# TopLevel.net
KiCad netlist of a schematic drawn in Altium Designer
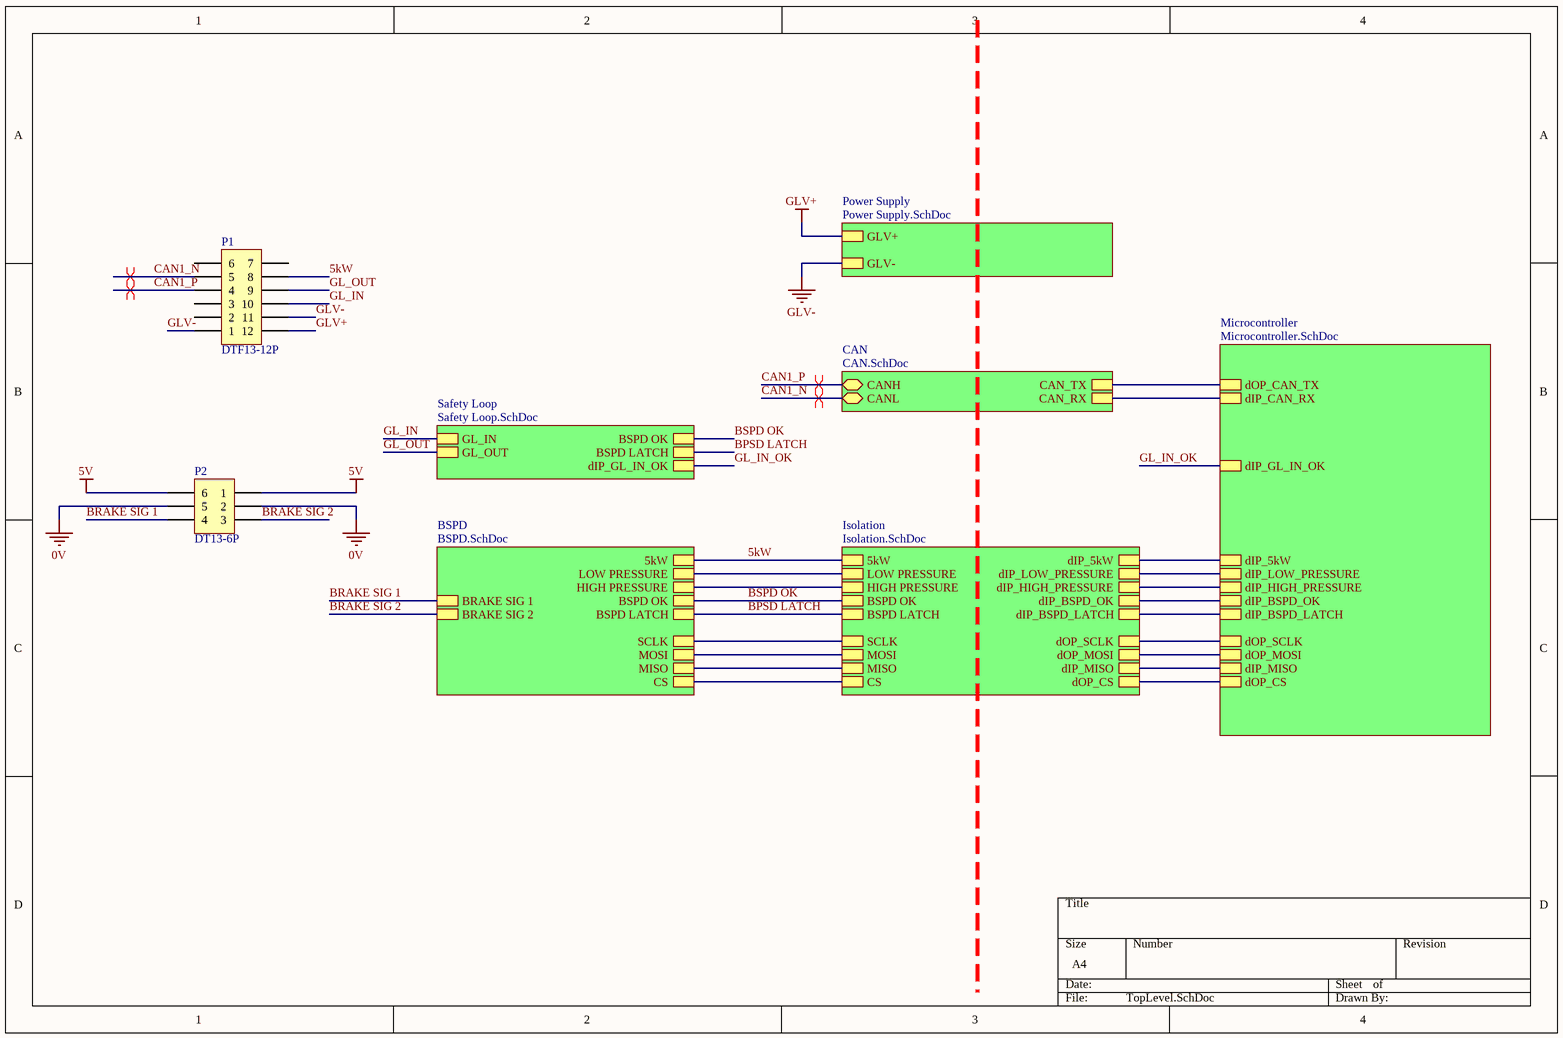
[diagram p0: TopLevel.SchDoc]

(export (version "E")
  (design (tool "Eeschema 10.0.6"))
  (components
    (comp (ref "P1")
      (value "DTF13-12P")
      (footprint "DTF13-12P")
      (fields (field (name "DIGIKEY PART NUMBER") "1734-1861-ND") (field (name "CONTACT") "Copper Alloy"))
      (libsource (lib "ts_standard_connectors") (part "DT13-12P"))
    )
    (comp (ref "P2")
      (value "DT13-6P")
      (footprint "DTF13-6P")
      (fields
        (field (name "PART NUMBER") "DTF13-6P")
        (field (name "DIGIKEY PART NUMBER") "1734-1754-ND")
        (field (name "CONTACT") "Copper Alloy")
      )
      (libsource (lib "ts_standard_connectors") (part "DT13-6P"))
    )
  )
  (nets
    (net (code "1") (name "/5kW") (class "Default")
      (node (ref "P1") (pin "8") (pinfunction "8_8") (pintype "passive"))
    )
    (net (code "3") (name "/BRAKE SIG 1") (class "Default")
      (node (ref "P2") (pin "4") (pinfunction "4_4") (pintype "passive"))
    )
    (net (code "4") (name "/BRAKE SIG 2") (class "Default")
      (node (ref "P2") (pin "3") (pinfunction "3_3") (pintype "power_in"))
    )
    (net (code "6") (name "/CAN1_N") (class "Default")
      (node (ref "P1") (pin "5") (pinfunction "5_5") (pintype "power_in"))
    )
    (net (code "7") (name "/CAN1_P") (class "Default")
      (node (ref "P1") (pin "4") (pinfunction "4_4") (pintype "power_in"))
    )
    (net (code "11") (name "/GL_IN") (class "Default")
      (node (ref "P1") (pin "10") (pinfunction "10_10") (pintype "passive"))
    )
    (net (code "13") (name "/GL_OUT") (class "Default")
      (node (ref "P1") (pin "9") (pinfunction "9_9") (pintype "passive"))
    )
    (net (code "28") (name "0V") (class "Default")
      (node (ref "P2") (pin "2") (pinfunction "2_2") (pintype "power_in"))
      (node (ref "P2") (pin "5") (pinfunction "5_5") (pintype "passive"))
    )
    (net (code "29") (name "5V") (class "Default")
      (node (ref "P2") (pin "1") (pinfunction "1_1") (pintype "power_in"))
      (node (ref "P2") (pin "6") (pinfunction "6_6") (pintype "passive"))
    )
    (net (code "30") (name "GLV+") (class "Default")
      (node (ref "P1") (pin "12") (pinfunction "12_12") (pintype "passive"))
    )
    (net (code "31") (name "GLV-") (class "Default")
      (node (ref "P1") (pin "1") (pinfunction "1_1") (pintype "power_in"))
      (node (ref "P1") (pin "11") (pinfunction "11_11") (pintype "passive"))
    )
    (net (code "32") (name "unconnected-(P1-Pad2)") (class "Default")
      (node (ref "P1") (pin "2") (pinfunction "2_2") (pintype "power_in"))
    )
    (net (code "33") (name "unconnected-(P1-Pad3)") (class "Default")
      (node (ref "P1") (pin "3") (pinfunction "3_3") (pintype "power_in"))
    )
    (net (code "34") (name "unconnected-(P1-Pad6)") (class "Default")
      (node (ref "P1") (pin "6") (pinfunction "6_6") (pintype "power_in"))
    )
    (net (code "35") (name "unconnected-(P1-Pad7)") (class "Default")
      (node (ref "P1") (pin "7") (pinfunction "7_7") (pintype "passive"))
    )
  )
)
